# i2c_buffer.net
KiCad netlist of a schematic drawn in EAGLE
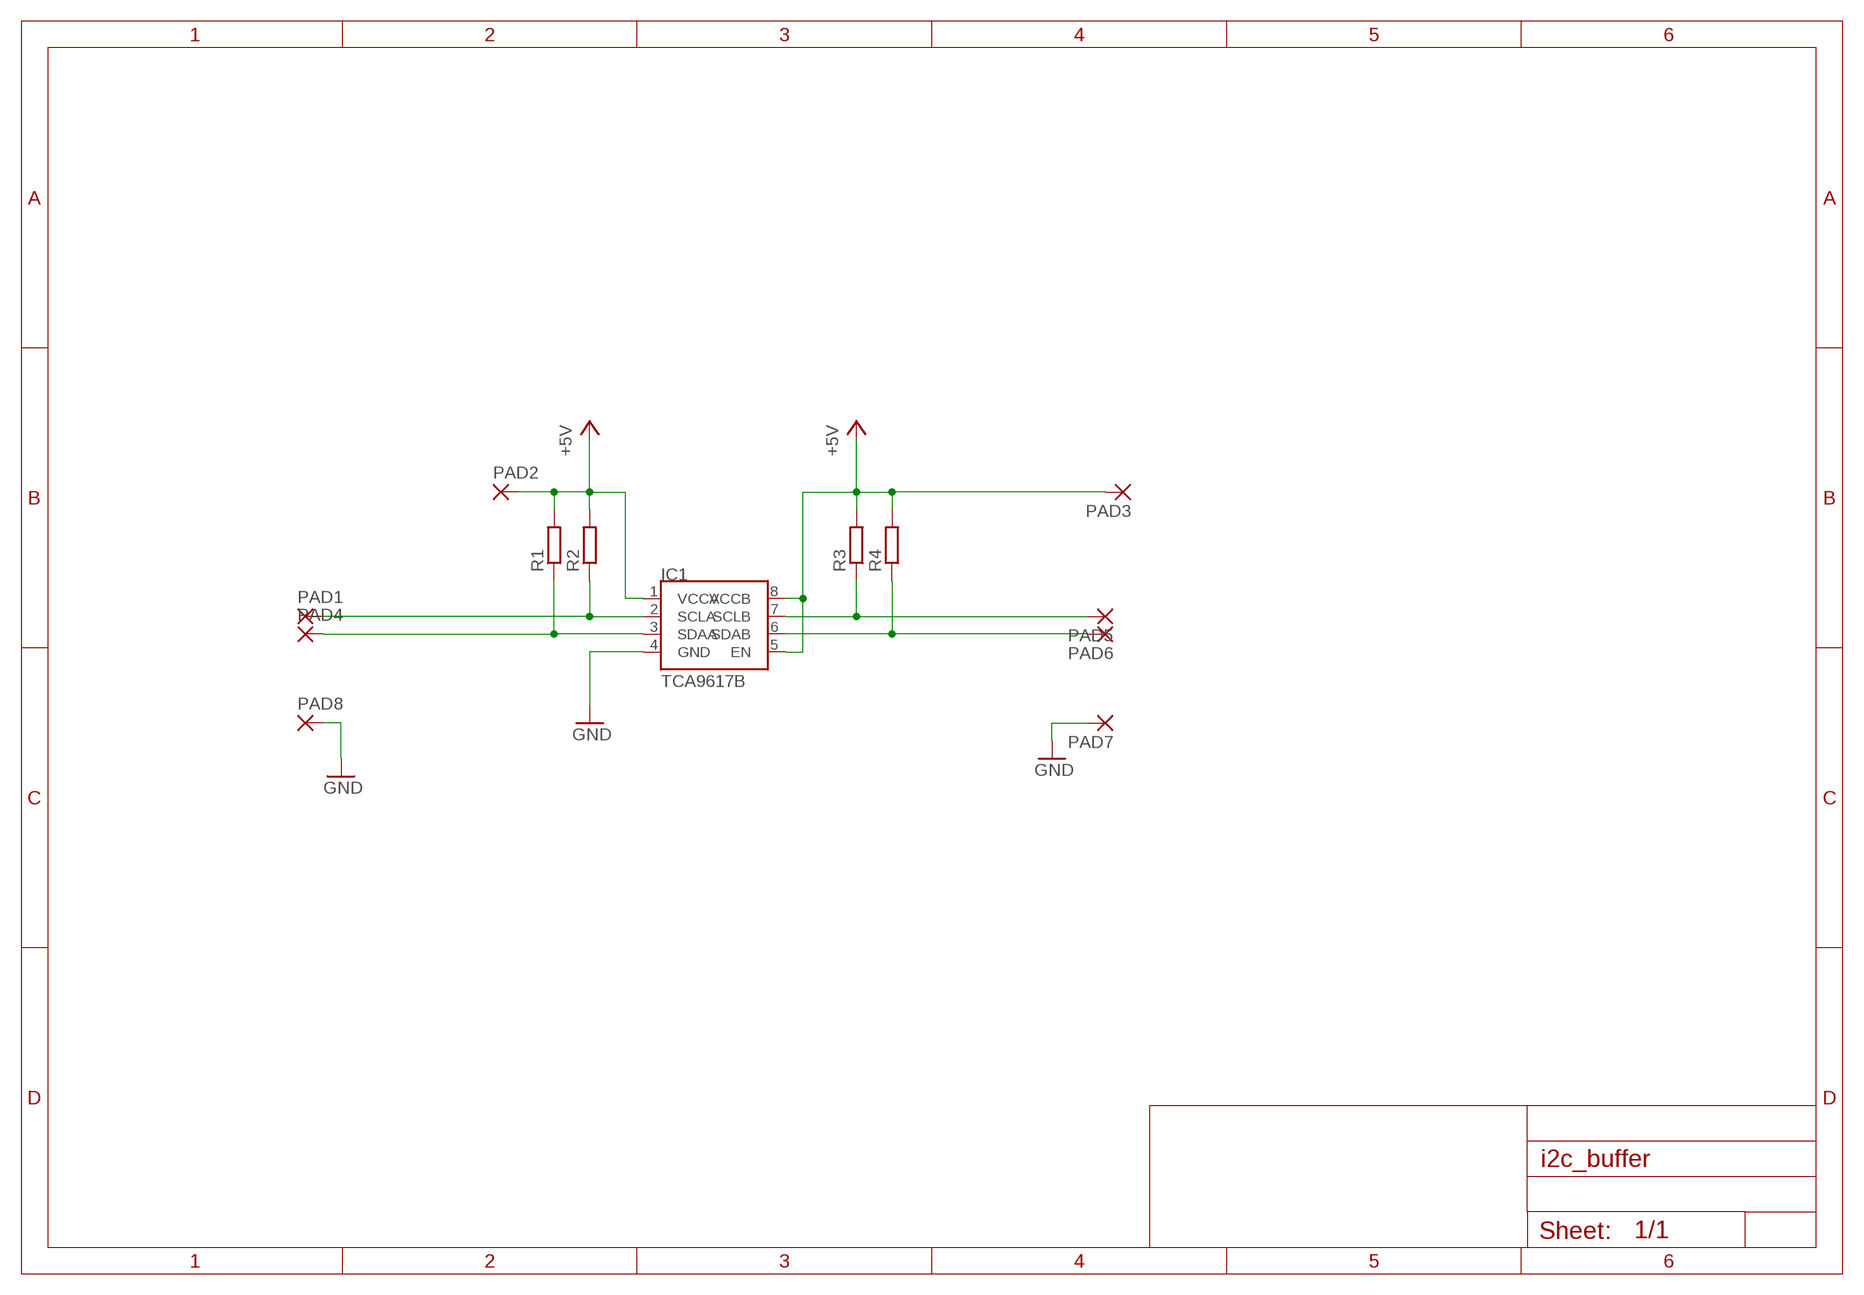
[diagram p0: schematic, sheet 1]

(export (version "E")
  (design (tool "Eeschema 10.0.6"))
  (components
    (comp (ref "IC1")
      (value "TCA9617B")
      (footprint "eagle-import:VSSOP-8")
      (libsource (lib "eagle-import") (part "TCA9617B"))
    )
    (comp (ref "PAD1")
      (value "2,15/1,0")
      (footprint "eagle-import:2,15_1,0")
      (libsource (lib "eagle-import") (part "2,15/1,0"))
    )
    (comp (ref "PAD2")
      (value "2,15/1,0")
      (footprint "eagle-import:2,15_1,0")
      (libsource (lib "eagle-import") (part "2,15/1,0"))
    )
    (comp (ref "PAD3")
      (value "2,15/1,0")
      (footprint "eagle-import:2,15_1,0")
      (libsource (lib "eagle-import") (part "2,15/1,0"))
    )
    (comp (ref "PAD4")
      (value "2,15/1,0")
      (footprint "eagle-import:2,15_1,0")
      (libsource (lib "eagle-import") (part "2,15/1,0"))
    )
    (comp (ref "PAD5")
      (value "2,15/1,0")
      (footprint "eagle-import:2,15_1,0")
      (libsource (lib "eagle-import") (part "2,15/1,0"))
    )
    (comp (ref "PAD6")
      (value "2,15/1,0")
      (footprint "eagle-import:2,15_1,0")
      (libsource (lib "eagle-import") (part "2,15/1,0"))
    )
    (comp (ref "PAD7")
      (value "2,15/1,0")
      (footprint "eagle-import:2,15_1,0")
      (libsource (lib "eagle-import") (part "2,15/1,0"))
    )
    (comp (ref "PAD8")
      (value "2,15/1,0")
      (footprint "eagle-import:2,15_1,0")
      (libsource (lib "eagle-import") (part "2,15/1,0"))
    )
    (comp (ref "R1")
      (value "R-EU_R0805")
      (footprint "eagle-import:R0805")
      (libsource (lib "eagle-import") (part "R-EU_R0805"))
    )
    (comp (ref "R2")
      (value "R-EU_R0805")
      (footprint "eagle-import:R0805")
      (libsource (lib "eagle-import") (part "R-EU_R0805"))
    )
    (comp (ref "R3")
      (value "R-EU_R0805")
      (footprint "eagle-import:R0805")
      (libsource (lib "eagle-import") (part "R-EU_R0805"))
    )
    (comp (ref "R4")
      (value "R-EU_R0805")
      (footprint "eagle-import:R0805")
      (libsource (lib "eagle-import") (part "R-EU_R0805"))
    )
  )
  (nets
    (net (code "1") (name "+5V") (class "Default")
      (node (ref "IC1") (pin "1") (pinfunction "VCCA_1") (pintype "bidirectional"))
      (node (ref "IC1") (pin "5") (pinfunction "EN_5") (pintype "bidirectional"))
      (node (ref "IC1") (pin "8") (pinfunction "VCCB_8") (pintype "bidirectional"))
      (node (ref "PAD2") (pin "1") (pinfunction "P_1") (pintype "passive"))
      (node (ref "PAD3") (pin "1") (pinfunction "P_1") (pintype "passive"))
      (node (ref "R1") (pin "2") (pinfunction "2_2") (pintype "passive"))
      (node (ref "R2") (pin "2") (pinfunction "2_2") (pintype "passive"))
      (node (ref "R3") (pin "2") (pinfunction "2_2") (pintype "passive"))
      (node (ref "R4") (pin "2") (pinfunction "2_2") (pintype "passive"))
    )
    (net (code "2") (name "GND") (class "Default")
      (node (ref "IC1") (pin "4") (pinfunction "GND_4") (pintype "bidirectional"))
      (node (ref "PAD7") (pin "1") (pinfunction "P_1") (pintype "passive"))
      (node (ref "PAD8") (pin "1") (pinfunction "P_1") (pintype "passive"))
    )
    (net (code "3") (name "Net-(IC1-SCLA)") (class "Default")
      (node (ref "IC1") (pin "2") (pinfunction "SCLA_2") (pintype "bidirectional"))
      (node (ref "PAD1") (pin "1") (pinfunction "P_1") (pintype "passive"))
      (node (ref "R2") (pin "1") (pinfunction "1_1") (pintype "passive"))
    )
    (net (code "4") (name "Net-(IC1-SCLB)") (class "Default")
      (node (ref "IC1") (pin "7") (pinfunction "SCLB_7") (pintype "bidirectional"))
      (node (ref "PAD5") (pin "1") (pinfunction "P_1") (pintype "passive"))
      (node (ref "R3") (pin "1") (pinfunction "1_1") (pintype "passive"))
    )
    (net (code "5") (name "Net-(IC1-SDAA)") (class "Default")
      (node (ref "IC1") (pin "3") (pinfunction "SDAA_3") (pintype "bidirectional"))
      (node (ref "PAD4") (pin "1") (pinfunction "P_1") (pintype "passive"))
      (node (ref "R1") (pin "1") (pinfunction "1_1") (pintype "passive"))
    )
    (net (code "6") (name "Net-(IC1-SDAB)") (class "Default")
      (node (ref "IC1") (pin "6") (pinfunction "SDAB_6") (pintype "bidirectional"))
      (node (ref "PAD6") (pin "1") (pinfunction "P_1") (pintype "passive"))
      (node (ref "R4") (pin "1") (pinfunction "1_1") (pintype "passive"))
    )
  )
)
